# DSP1.net
KiCad netlist of a schematic drawn in Altium Designer
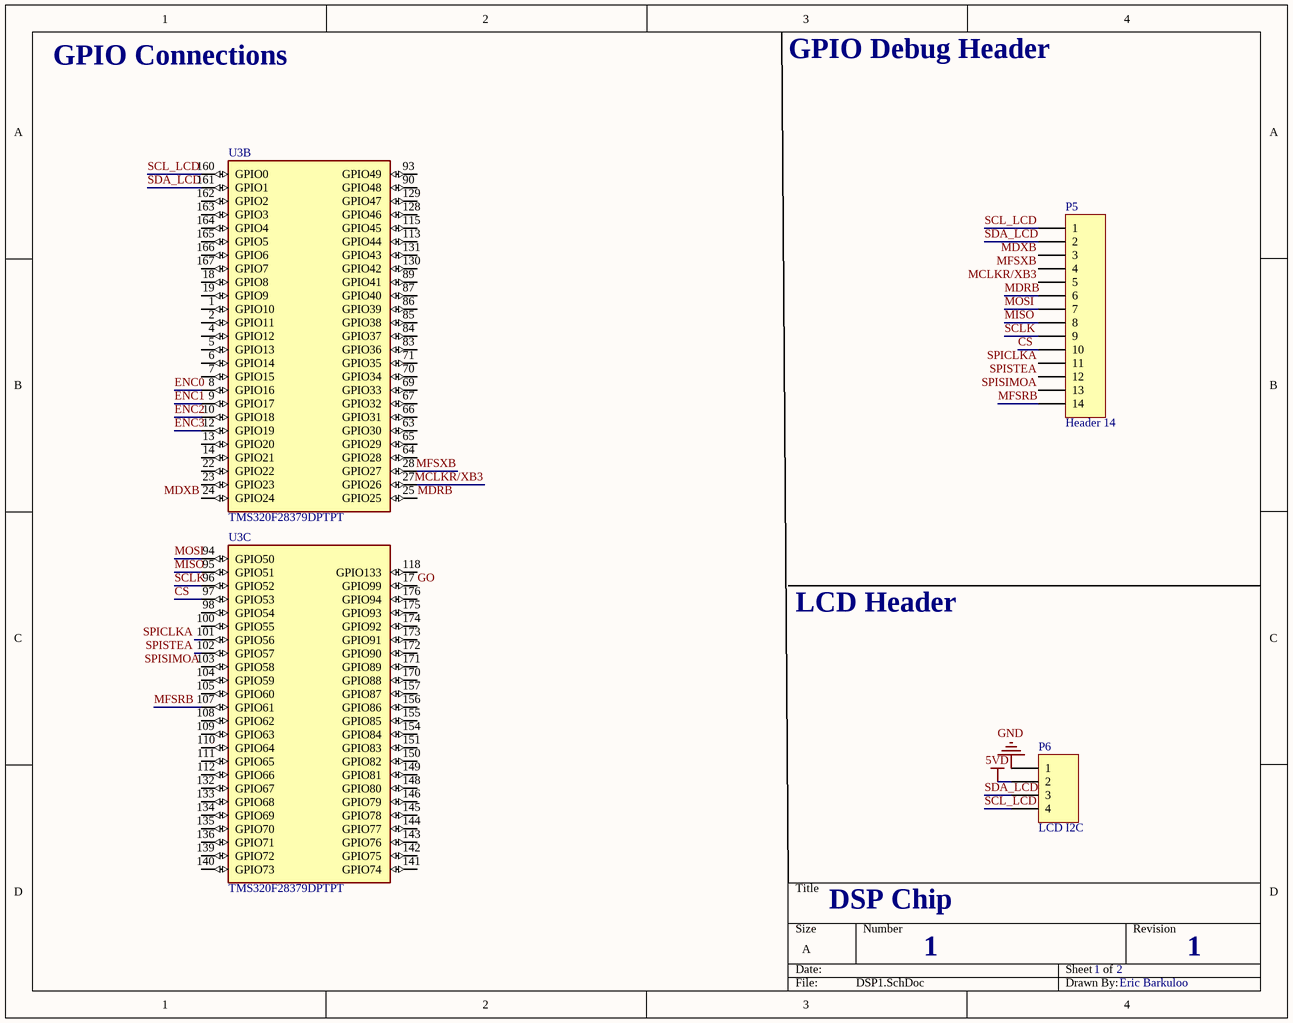
[diagram p0: DSP1.SchDoc]

(export (version "E")
  (design (tool "Eeschema 10.0.6"))
  (components
    (comp (ref "P5")
      (value "Header 14")
      (footprint "HDR1X14")
      (description "Header, 14-Pin")
      (fields (field (name "PUBLISHER") "Altium Limited"))
      (libsource (lib "Miscellaneous Connectors") (part "Header 14"))
    )
    (comp (ref "P6")
      (value "LCD I2C")
      (footprint "HDR1X4H")
      (description "Header, 4-Pin, Right Angle")
      (fields (field (name "PUBLISHER") "Altium Limited"))
      (libsource (lib "Miscellaneous Connectors") (part "Header 4H"))
    )
    (comp (ref "U3")
      (value "TMS320F28379DPTPT")
      (footprint "IC_TMS320F28379DPTPT")
      (libsource (lib "TMS320F28379DPTPT") (part "TMS320F28379DPTPT"))
    )
  )
  (nets
    (net (code "1") (name "/CS") (class "Default")
      (node (ref "P5") (pin "10") (pinfunction "10_10") (pintype "passive"))
      (node (ref "U3") (pin "97") (pinfunction "GPIO53_97") (pintype "bidirectional"))
    )
    (net (code "2") (name "/ENC0") (class "Default")
      (node (ref "U3") (pin "8") (pinfunction "GPIO16_8") (pintype "bidirectional"))
    )
    (net (code "3") (name "/ENC1") (class "Default")
      (node (ref "U3") (pin "9") (pinfunction "GPIO17_9") (pintype "bidirectional"))
    )
    (net (code "4") (name "/ENC2") (class "Default")
      (node (ref "U3") (pin "10") (pinfunction "GPIO18_10") (pintype "bidirectional"))
    )
    (net (code "5") (name "/ENC3") (class "Default")
      (node (ref "U3") (pin "12") (pinfunction "GPIO19_12") (pintype "bidirectional"))
    )
    (net (code "6") (name "/GO") (class "Default")
      (node (ref "U3") (pin "17") (pinfunction "GPIO99_17") (pintype "bidirectional"))
    )
    (net (code "7") (name "/MCLKR{slash}XB3") (class "Default")
      (node (ref "P5") (pin "5") (pinfunction "5_5") (pintype "passive"))
      (node (ref "U3") (pin "27") (pinfunction "GPIO26_27") (pintype "bidirectional"))
    )
    (net (code "8") (name "/MDRB") (class "Default")
      (node (ref "P5") (pin "6") (pinfunction "6_6") (pintype "passive"))
      (node (ref "U3") (pin "25") (pinfunction "GPIO25_25") (pintype "bidirectional"))
    )
    (net (code "9") (name "/MDXB") (class "Default")
      (node (ref "P5") (pin "3") (pinfunction "3_3") (pintype "passive"))
      (node (ref "U3") (pin "24") (pinfunction "GPIO24_24") (pintype "bidirectional"))
    )
    (net (code "10") (name "/MFSRB") (class "Default")
      (node (ref "P5") (pin "14") (pinfunction "14_14") (pintype "passive"))
      (node (ref "U3") (pin "107") (pinfunction "GPIO61_107") (pintype "bidirectional"))
    )
    (net (code "11") (name "/MFSXB") (class "Default")
      (node (ref "P5") (pin "4") (pinfunction "4_4") (pintype "passive"))
      (node (ref "U3") (pin "28") (pinfunction "GPIO27_28") (pintype "bidirectional"))
    )
    (net (code "12") (name "/MISO") (class "Default")
      (node (ref "P5") (pin "8") (pinfunction "8_8") (pintype "passive"))
      (node (ref "U3") (pin "95") (pinfunction "GPIO51_95") (pintype "bidirectional"))
    )
    (net (code "13") (name "/MOSI") (class "Default")
      (node (ref "P5") (pin "7") (pinfunction "7_7") (pintype "passive"))
      (node (ref "U3") (pin "94") (pinfunction "GPIO50_94") (pintype "bidirectional"))
    )
    (net (code "14") (name "/SCLK") (class "Default")
      (node (ref "P5") (pin "9") (pinfunction "9_9") (pintype "passive"))
      (node (ref "U3") (pin "96") (pinfunction "GPIO52_96") (pintype "bidirectional"))
    )
    (net (code "15") (name "/SCL_LCD") (class "Default")
      (node (ref "P5") (pin "1") (pinfunction "1_1") (pintype "passive"))
      (node (ref "P6") (pin "4") (pinfunction "4_4") (pintype "passive"))
      (node (ref "U3") (pin "160") (pinfunction "GPIO0_160") (pintype "bidirectional"))
    )
    (net (code "16") (name "/SDA_LCD") (class "Default")
      (node (ref "P5") (pin "2") (pinfunction "2_2") (pintype "passive"))
      (node (ref "P6") (pin "3") (pinfunction "3_3") (pintype "passive"))
      (node (ref "U3") (pin "161") (pinfunction "GPIO1_161") (pintype "bidirectional"))
    )
    (net (code "17") (name "/SPICLKA") (class "Default")
      (node (ref "P5") (pin "11") (pinfunction "11_11") (pintype "passive"))
      (node (ref "U3") (pin "101") (pinfunction "GPIO56_101") (pintype "bidirectional"))
    )
    (net (code "18") (name "/SPISIMOA") (class "Default")
      (node (ref "P5") (pin "13") (pinfunction "13_13") (pintype "passive"))
      (node (ref "U3") (pin "103") (pinfunction "GPIO58_103") (pintype "bidirectional"))
    )
    (net (code "19") (name "/SPISTEA") (class "Default")
      (node (ref "P5") (pin "12") (pinfunction "12_12") (pintype "passive"))
      (node (ref "U3") (pin "102") (pinfunction "GPIO57_102") (pintype "bidirectional"))
    )
    (net (code "20") (name "5VD") (class "Default")
      (node (ref "P6") (pin "2") (pinfunction "2_2") (pintype "passive"))
    )
    (net (code "21") (name "GND") (class "Default")
      (node (ref "P6") (pin "1") (pinfunction "1_1") (pintype "passive"))
    )
    (net (code "22") (name "unconnected-(U3B-GPIO2-Pad162)") (class "Default")
      (node (ref "U3") (pin "162") (pinfunction "GPIO2_162") (pintype "bidirectional"))
    )
    (net (code "23") (name "unconnected-(U3B-GPIO3-Pad163)") (class "Default")
      (node (ref "U3") (pin "163") (pinfunction "GPIO3_163") (pintype "bidirectional"))
    )
    (net (code "24") (name "unconnected-(U3B-GPIO4-Pad164)") (class "Default")
      (node (ref "U3") (pin "164") (pinfunction "GPIO4_164") (pintype "bidirectional"))
    )
    (net (code "25") (name "unconnected-(U3B-GPIO5-Pad165)") (class "Default")
      (node (ref "U3") (pin "165") (pinfunction "GPIO5_165") (pintype "bidirectional"))
    )
    (net (code "26") (name "unconnected-(U3B-GPIO6-Pad166)") (class "Default")
      (node (ref "U3") (pin "166") (pinfunction "GPIO6_166") (pintype "bidirectional"))
    )
    (net (code "27") (name "unconnected-(U3B-GPIO7-Pad167)") (class "Default")
      (node (ref "U3") (pin "167") (pinfunction "GPIO7_167") (pintype "bidirectional"))
    )
    (net (code "28") (name "unconnected-(U3B-GPIO8-Pad18)") (class "Default")
      (node (ref "U3") (pin "18") (pinfunction "GPIO8_18") (pintype "bidirectional"))
    )
    (net (code "29") (name "unconnected-(U3B-GPIO9-Pad19)") (class "Default")
      (node (ref "U3") (pin "19") (pinfunction "GPIO9_19") (pintype "bidirectional"))
    )
    (net (code "30") (name "unconnected-(U3B-GPIO10-Pad1)") (class "Default")
      (node (ref "U3") (pin "1") (pinfunction "GPIO10_1") (pintype "bidirectional"))
    )
    (net (code "31") (name "unconnected-(U3B-GPIO11-Pad2)") (class "Default")
      (node (ref "U3") (pin "2") (pinfunction "GPIO11_2") (pintype "bidirectional"))
    )
    (net (code "32") (name "unconnected-(U3B-GPIO12-Pad4)") (class "Default")
      (node (ref "U3") (pin "4") (pinfunction "GPIO12_4") (pintype "bidirectional"))
    )
    (net (code "33") (name "unconnected-(U3B-GPIO13-Pad5)") (class "Default")
      (node (ref "U3") (pin "5") (pinfunction "GPIO13_5") (pintype "bidirectional"))
    )
    (net (code "34") (name "unconnected-(U3B-GPIO14-Pad6)") (class "Default")
      (node (ref "U3") (pin "6") (pinfunction "GPIO14_6") (pintype "bidirectional"))
    )
    (net (code "35") (name "unconnected-(U3B-GPIO15-Pad7)") (class "Default")
      (node (ref "U3") (pin "7") (pinfunction "GPIO15_7") (pintype "bidirectional"))
    )
    (net (code "36") (name "unconnected-(U3B-GPIO20-Pad13)") (class "Default")
      (node (ref "U3") (pin "13") (pinfunction "GPIO20_13") (pintype "bidirectional"))
    )
    (net (code "37") (name "unconnected-(U3B-GPIO21-Pad14)") (class "Default")
      (node (ref "U3") (pin "14") (pinfunction "GPIO21_14") (pintype "bidirectional"))
    )
    (net (code "38") (name "unconnected-(U3B-GPIO22-Pad22)") (class "Default")
      (node (ref "U3") (pin "22") (pinfunction "GPIO22_22") (pintype "bidirectional"))
    )
    (net (code "39") (name "unconnected-(U3B-GPIO23-Pad23)") (class "Default")
      (node (ref "U3") (pin "23") (pinfunction "GPIO23_23") (pintype "bidirectional"))
    )
    (net (code "40") (name "unconnected-(U3B-GPIO28-Pad64)") (class "Default")
      (node (ref "U3") (pin "64") (pinfunction "GPIO28_64") (pintype "bidirectional"))
    )
    (net (code "41") (name "unconnected-(U3B-GPIO29-Pad65)") (class "Default")
      (node (ref "U3") (pin "65") (pinfunction "GPIO29_65") (pintype "bidirectional"))
    )
    (net (code "42") (name "unconnected-(U3B-GPIO30-Pad63)") (class "Default")
      (node (ref "U3") (pin "63") (pinfunction "GPIO30_63") (pintype "bidirectional"))
    )
    (net (code "43") (name "unconnected-(U3B-GPIO31-Pad66)") (class "Default")
      (node (ref "U3") (pin "66") (pinfunction "GPIO31_66") (pintype "bidirectional"))
    )
    (net (code "44") (name "unconnected-(U3B-GPIO32-Pad67)") (class "Default")
      (node (ref "U3") (pin "67") (pinfunction "GPIO32_67") (pintype "bidirectional"))
    )
    (net (code "45") (name "unconnected-(U3B-GPIO33-Pad69)") (class "Default")
      (node (ref "U3") (pin "69") (pinfunction "GPIO33_69") (pintype "bidirectional"))
    )
    (net (code "46") (name "unconnected-(U3B-GPIO34-Pad70)") (class "Default")
      (node (ref "U3") (pin "70") (pinfunction "GPIO34_70") (pintype "bidirectional"))
    )
    (net (code "47") (name "unconnected-(U3B-GPIO35-Pad71)") (class "Default")
      (node (ref "U3") (pin "71") (pinfunction "GPIO35_71") (pintype "bidirectional"))
    )
    (net (code "48") (name "unconnected-(U3B-GPIO36-Pad83)") (class "Default")
      (node (ref "U3") (pin "83") (pinfunction "GPIO36_83") (pintype "bidirectional"))
    )
    (net (code "49") (name "unconnected-(U3B-GPIO37-Pad84)") (class "Default")
      (node (ref "U3") (pin "84") (pinfunction "GPIO37_84") (pintype "bidirectional"))
    )
    (net (code "50") (name "unconnected-(U3B-GPIO38-Pad85)") (class "Default")
      (node (ref "U3") (pin "85") (pinfunction "GPIO38_85") (pintype "bidirectional"))
    )
    (net (code "51") (name "unconnected-(U3B-GPIO39-Pad86)") (class "Default")
      (node (ref "U3") (pin "86") (pinfunction "GPIO39_86") (pintype "bidirectional"))
    )
    (net (code "52") (name "unconnected-(U3B-GPIO40-Pad87)") (class "Default")
      (node (ref "U3") (pin "87") (pinfunction "GPIO40_87") (pintype "bidirectional"))
    )
    (net (code "53") (name "unconnected-(U3B-GPIO41-Pad89)") (class "Default")
      (node (ref "U3") (pin "89") (pinfunction "GPIO41_89") (pintype "bidirectional"))
    )
    (net (code "54") (name "unconnected-(U3B-GPIO42-Pad130)") (class "Default")
      (node (ref "U3") (pin "130") (pinfunction "GPIO42_130") (pintype "bidirectional"))
    )
    (net (code "55") (name "unconnected-(U3B-GPIO43-Pad131)") (class "Default")
      (node (ref "U3") (pin "131") (pinfunction "GPIO43_131") (pintype "bidirectional"))
    )
    (net (code "56") (name "unconnected-(U3B-GPIO44-Pad113)") (class "Default")
      (node (ref "U3") (pin "113") (pinfunction "GPIO44_113") (pintype "bidirectional"))
    )
    (net (code "57") (name "unconnected-(U3B-GPIO45-Pad115)") (class "Default")
      (node (ref "U3") (pin "115") (pinfunction "GPIO45_115") (pintype "bidirectional"))
    )
    (net (code "58") (name "unconnected-(U3B-GPIO46-Pad128)") (class "Default")
      (node (ref "U3") (pin "128") (pinfunction "GPIO46_128") (pintype "bidirectional"))
    )
    (net (code "59") (name "unconnected-(U3B-GPIO47-Pad129)") (class "Default")
      (node (ref "U3") (pin "129") (pinfunction "GPIO47_129") (pintype "bidirectional"))
    )
    (net (code "60") (name "unconnected-(U3B-GPIO48-Pad90)") (class "Default")
      (node (ref "U3") (pin "90") (pinfunction "GPIO48_90") (pintype "bidirectional"))
    )
    (net (code "61") (name "unconnected-(U3B-GPIO49-Pad93)") (class "Default")
      (node (ref "U3") (pin "93") (pinfunction "GPIO49_93") (pintype "bidirectional"))
    )
    (net (code "62") (name "unconnected-(U3C-GPIO54-Pad98)") (class "Default")
      (node (ref "U3") (pin "98") (pinfunction "GPIO54_98") (pintype "bidirectional"))
    )
    (net (code "63") (name "unconnected-(U3C-GPIO55-Pad100)") (class "Default")
      (node (ref "U3") (pin "100") (pinfunction "GPIO55_100") (pintype "bidirectional"))
    )
    (net (code "64") (name "unconnected-(U3C-GPIO59-Pad104)") (class "Default")
      (node (ref "U3") (pin "104") (pinfunction "GPIO59_104") (pintype "bidirectional"))
    )
    (net (code "65") (name "unconnected-(U3C-GPIO60-Pad105)") (class "Default")
      (node (ref "U3") (pin "105") (pinfunction "GPIO60_105") (pintype "bidirectional"))
    )
    (net (code "66") (name "unconnected-(U3C-GPIO62-Pad108)") (class "Default")
      (node (ref "U3") (pin "108") (pinfunction "GPIO62_108") (pintype "bidirectional"))
    )
    (net (code "67") (name "unconnected-(U3C-GPIO63-Pad109)") (class "Default")
      (node (ref "U3") (pin "109") (pinfunction "GPIO63_109") (pintype "bidirectional"))
    )
    (net (code "68") (name "unconnected-(U3C-GPIO64-Pad110)") (class "Default")
      (node (ref "U3") (pin "110") (pinfunction "GPIO64_110") (pintype "bidirectional"))
    )
    (net (code "69") (name "unconnected-(U3C-GPIO65-Pad111)") (class "Default")
      (node (ref "U3") (pin "111") (pinfunction "GPIO65_111") (pintype "bidirectional"))
    )
    (net (code "70") (name "unconnected-(U3C-GPIO66-Pad112)") (class "Default")
      (node (ref "U3") (pin "112") (pinfunction "GPIO66_112") (pintype "bidirectional"))
    )
    (net (code "71") (name "unconnected-(U3C-GPIO67-Pad132)") (class "Default")
      (node (ref "U3") (pin "132") (pinfunction "GPIO67_132") (pintype "bidirectional"))
    )
    (net (code "72") (name "unconnected-(U3C-GPIO68-Pad133)") (class "Default")
      (node (ref "U3") (pin "133") (pinfunction "GPIO68_133") (pintype "bidirectional"))
    )
    (net (code "73") (name "unconnected-(U3C-GPIO69-Pad134)") (class "Default")
      (node (ref "U3") (pin "134") (pinfunction "GPIO69_134") (pintype "bidirectional"))
    )
    (net (code "74") (name "unconnected-(U3C-GPIO70-Pad135)") (class "Default")
      (node (ref "U3") (pin "135") (pinfunction "GPIO70_135") (pintype "bidirectional"))
    )
    (net (code "75") (name "unconnected-(U3C-GPIO71-Pad136)") (class "Default")
      (node (ref "U3") (pin "136") (pinfunction "GPIO71_136") (pintype "bidirectional"))
    )
    (net (code "76") (name "unconnected-(U3C-GPIO72-Pad139)") (class "Default")
      (node (ref "U3") (pin "139") (pinfunction "GPIO72_139") (pintype "bidirectional"))
    )
    (net (code "77") (name "unconnected-(U3C-GPIO73-Pad140)") (class "Default")
      (node (ref "U3") (pin "140") (pinfunction "GPIO73_140") (pintype "bidirectional"))
    )
    (net (code "78") (name "unconnected-(U3C-GPIO74-Pad141)") (class "Default")
      (node (ref "U3") (pin "141") (pinfunction "GPIO74_141") (pintype "bidirectional"))
    )
    (net (code "79") (name "unconnected-(U3C-GPIO75-Pad142)") (class "Default")
      (node (ref "U3") (pin "142") (pinfunction "GPIO75_142") (pintype "bidirectional"))
    )
    (net (code "80") (name "unconnected-(U3C-GPIO76-Pad143)") (class "Default")
      (node (ref "U3") (pin "143") (pinfunction "GPIO76_143") (pintype "bidirectional"))
    )
    (net (code "81") (name "unconnected-(U3C-GPIO77-Pad144)") (class "Default")
      (node (ref "U3") (pin "144") (pinfunction "GPIO77_144") (pintype "bidirectional"))
    )
    (net (code "82") (name "unconnected-(U3C-GPIO78-Pad145)") (class "Default")
      (node (ref "U3") (pin "145") (pinfunction "GPIO78_145") (pintype "bidirectional"))
    )
    (net (code "83") (name "unconnected-(U3C-GPIO79-Pad146)") (class "Default")
      (node (ref "U3") (pin "146") (pinfunction "GPIO79_146") (pintype "bidirectional"))
    )
    (net (code "84") (name "unconnected-(U3C-GPIO80-Pad148)") (class "Default")
      (node (ref "U3") (pin "148") (pinfunction "GPIO80_148") (pintype "bidirectional"))
    )
    (net (code "85") (name "unconnected-(U3C-GPIO81-Pad149)") (class "Default")
      (node (ref "U3") (pin "149") (pinfunction "GPIO81_149") (pintype "bidirectional"))
    )
    (net (code "86") (name "unconnected-(U3C-GPIO82-Pad150)") (class "Default")
      (node (ref "U3") (pin "150") (pinfunction "GPIO82_150") (pintype "bidirectional"))
    )
    (net (code "87") (name "unconnected-(U3C-GPIO83-Pad151)") (class "Default")
      (node (ref "U3") (pin "151") (pinfunction "GPIO83_151") (pintype "bidirectional"))
    )
    (net (code "88") (name "unconnected-(U3C-GPIO84-Pad154)") (class "Default")
      (node (ref "U3") (pin "154") (pinfunction "GPIO84_154") (pintype "bidirectional"))
    )
    (net (code "89") (name "unconnected-(U3C-GPIO85-Pad155)") (class "Default")
      (node (ref "U3") (pin "155") (pinfunction "GPIO85_155") (pintype "bidirectional"))
    )
    (net (code "90") (name "unconnected-(U3C-GPIO86-Pad156)") (class "Default")
      (node (ref "U3") (pin "156") (pinfunction "GPIO86_156") (pintype "bidirectional"))
    )
    (net (code "91") (name "unconnected-(U3C-GPIO87-Pad157)") (class "Default")
      (node (ref "U3") (pin "157") (pinfunction "GPIO87_157") (pintype "bidirectional"))
    )
    (net (code "92") (name "unconnected-(U3C-GPIO88-Pad170)") (class "Default")
      (node (ref "U3") (pin "170") (pinfunction "GPIO88_170") (pintype "bidirectional"))
    )
    (net (code "93") (name "unconnected-(U3C-GPIO89-Pad171)") (class "Default")
      (node (ref "U3") (pin "171") (pinfunction "GPIO89_171") (pintype "bidirectional"))
    )
    (net (code "94") (name "unconnected-(U3C-GPIO90-Pad172)") (class "Default")
      (node (ref "U3") (pin "172") (pinfunction "GPIO90_172") (pintype "bidirectional"))
    )
    (net (code "95") (name "unconnected-(U3C-GPIO91-Pad173)") (class "Default")
      (node (ref "U3") (pin "173") (pinfunction "GPIO91_173") (pintype "bidirectional"))
    )
    (net (code "96") (name "unconnected-(U3C-GPIO92-Pad174)") (class "Default")
      (node (ref "U3") (pin "174") (pinfunction "GPIO92_174") (pintype "bidirectional"))
    )
    (net (code "97") (name "unconnected-(U3C-GPIO93-Pad175)") (class "Default")
      (node (ref "U3") (pin "175") (pinfunction "GPIO93_175") (pintype "bidirectional"))
    )
    (net (code "98") (name "unconnected-(U3C-GPIO94-Pad176)") (class "Default")
      (node (ref "U3") (pin "176") (pinfunction "GPIO94_176") (pintype "bidirectional"))
    )
    (net (code "99") (name "unconnected-(U3C-GPIO133-Pad118)") (class "Default")
      (node (ref "U3") (pin "118") (pinfunction "GPIO133_118") (pintype "bidirectional"))
    )
  )
)
